# Nanite_85_SS.net
KiCad netlist of a schematic drawn in EAGLE
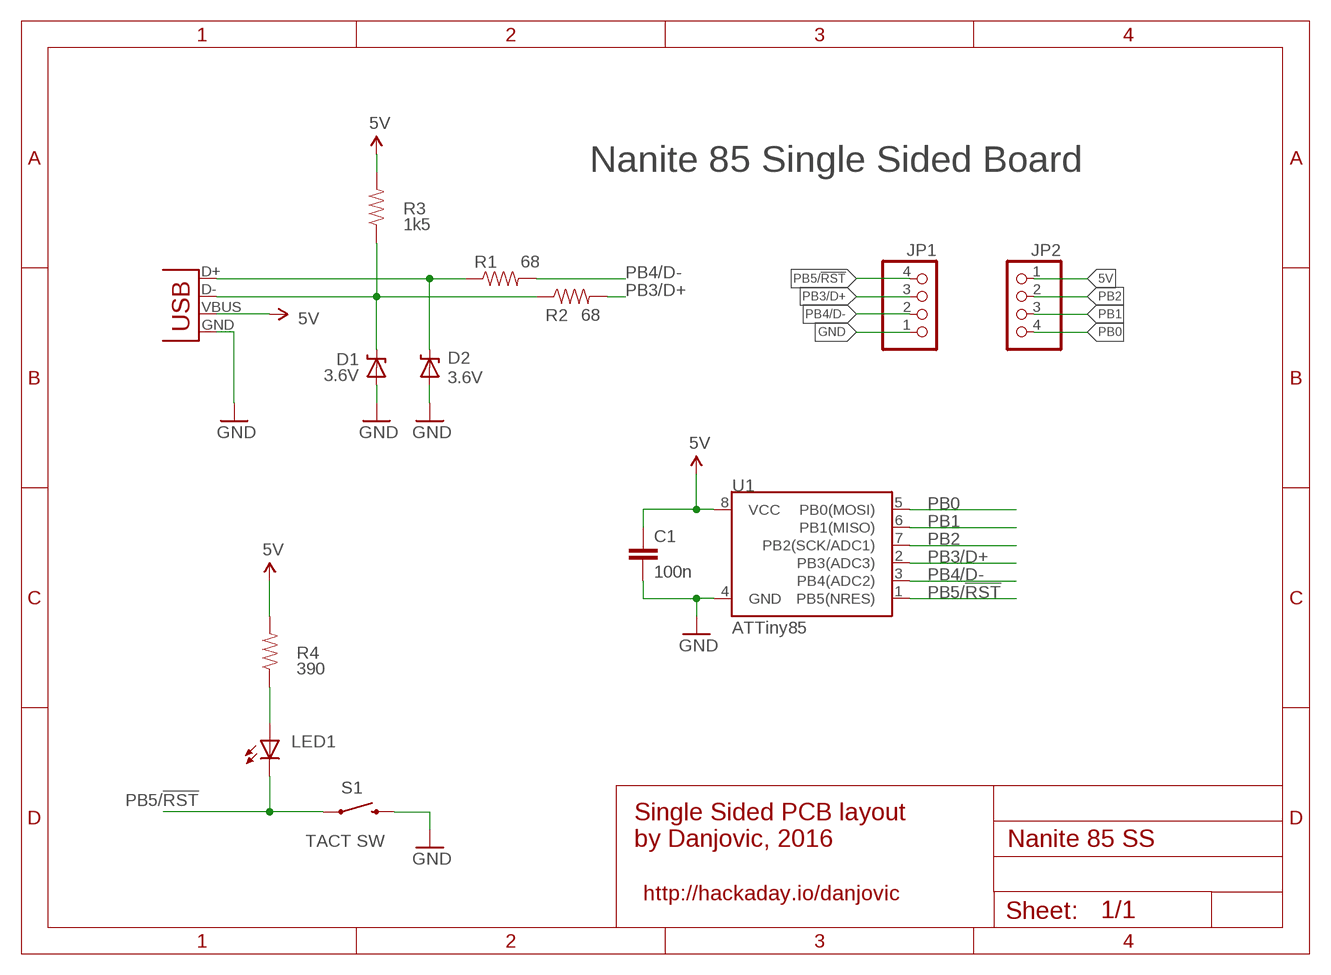
[diagram p0: schematic, sheet 1]

(export (version "E")
  (design (tool "Eeschema 10.0.6"))
  (components
    (comp (ref "C1")
      (value "100n")
      (footprint "eagle-import:CAP-PTH-SMALL-KIT")
      (libsource (lib "eagle-import") (part "CAPKIT"))
    )
    (comp (ref "D1")
      (value "3.6V")
      (footprint "eagle-import:DIODE-ZENER")
      (libsource (lib "eagle-import") (part "DIODE-ZENERPTH"))
    )
    (comp (ref "D2")
      (value "3.6V")
      (footprint "eagle-import:DIODE-ZENER")
      (libsource (lib "eagle-import") (part "DIODE-ZENERPTH"))
    )
    (comp (ref "JP1")
      (value "HEADER-1X4ROUND")
      (footprint "eagle-import:1X04_ROUND")
      (libsource (lib "eagle-import") (part "HEADER-1X4ROUND"))
    )
    (comp (ref "JP2")
      (value "HEADER-1X4ROUND")
      (footprint "eagle-import:1X04_ROUND")
      (libsource (lib "eagle-import") (part "HEADER-1X4ROUND"))
    )
    (comp (ref "JP4")
      (value "USB-B")
      (footprint "eagle-import:USB-B-PTH")
      (libsource (lib "eagle-import") (part "USBPTH"))
    )
    (comp (ref "LED1")
      (value "LED3MM")
      (footprint "eagle-import:LED3MM")
      (libsource (lib "eagle-import") (part "LED3MM"))
    )
    (comp (ref "R1")
      (value "68")
      (footprint "eagle-import:AXIAL-0.3")
      (libsource (lib "eagle-import") (part "RESISTORAXIAL-0.3"))
    )
    (comp (ref "R2")
      (value "68")
      (footprint "eagle-import:AXIAL-0.3EZ")
      (libsource (lib "eagle-import") (part "RESISTOREZ"))
    )
    (comp (ref "R3")
      (value "1k5")
      (footprint "eagle-import:AXIAL-0.3EZ")
      (libsource (lib "eagle-import") (part "RESISTOREZ"))
    )
    (comp (ref "R4")
      (value "390")
      (footprint "eagle-import:AXIAL-0.3EZ")
      (libsource (lib "eagle-import") (part "RESISTOREZ"))
    )
    (comp (ref "S1")
      (value "TACT SW")
      (footprint "eagle-import:TACTILE-PTH")
      (libsource (lib "eagle-import") (part "SWITCH-MOMENTARY-2PTH"))
    )
    (comp (ref "U1")
      (value "ATTiny85")
      (footprint "eagle-import:DIP08")
      (libsource (lib "eagle-import") (part "ATTINY45TINY45-20-DIP"))
    )
  )
  (nets
    (net (code "1") (name "/PB5{slash}~{RST}") (class "Default")
      (node (ref "JP1") (pin "4") (pinfunction "4_4") (pintype "passive"))
      (node (ref "LED1") (pin "K") (pinfunction "C_K") (pintype "passive"))
      (node (ref "S1") (pin "1") (pinfunction "1_1") (pintype "passive"))
      (node (ref "U1") (pin "1") (pinfunction "PB5(NRES)_1") (pintype "bidirectional"))
    )
    (net (code "2") (name "5V") (class "Default")
      (node (ref "C1") (pin "1") (pinfunction "1_1") (pintype "passive"))
      (node (ref "JP2") (pin "1") (pinfunction "1_1") (pintype "passive"))
      (node (ref "JP4") (pin "VBUS") (pinfunction "VBUS_VBUS") (pintype "bidirectional"))
      (node (ref "R3") (pin "P$2") (pinfunction "2_P$2") (pintype "passive"))
      (node (ref "R4") (pin "P$2") (pinfunction "2_P$2") (pintype "passive"))
      (node (ref "U1") (pin "8") (pinfunction "VCC_8") (pintype "bidirectional"))
    )
    (net (code "3") (name "GND") (class "Default")
      (node (ref "C1") (pin "2") (pinfunction "2_2") (pintype "passive"))
      (node (ref "D1") (pin "P$2") (pinfunction "A_P$2") (pintype "passive"))
      (node (ref "D2") (pin "P$2") (pinfunction "A_P$2") (pintype "passive"))
      (node (ref "JP1") (pin "1") (pinfunction "1_1") (pintype "passive"))
      (node (ref "JP4") (pin "GND") (pinfunction "GND_GND") (pintype "bidirectional"))
      (node (ref "S1") (pin "3") (pinfunction "2_3") (pintype "passive"))
      (node (ref "U1") (pin "4") (pinfunction "GND_4") (pintype "bidirectional"))
    )
    (net (code "4") (name "Net-(D1-C)") (class "Default")
      (node (ref "D1") (pin "P$1") (pinfunction "C_P$1") (pintype "passive"))
      (node (ref "JP4") (pin "D-") (pinfunction "D-_D-") (pintype "bidirectional"))
      (node (ref "R2") (pin "P$1") (pinfunction "1_P$1") (pintype "passive"))
      (node (ref "R3") (pin "P$1") (pinfunction "1_P$1") (pintype "passive"))
    )
    (net (code "5") (name "Net-(D2-C)") (class "Default")
      (node (ref "D2") (pin "P$1") (pinfunction "C_P$1") (pintype "passive"))
      (node (ref "JP4") (pin "D+") (pinfunction "D+_D+") (pintype "bidirectional"))
      (node (ref "R1") (pin "P$1") (pinfunction "1_P$1") (pintype "passive"))
    )
    (net (code "6") (name "Net-(R4-1)") (class "Default")
      (node (ref "LED1") (pin "A") (pinfunction "A_A") (pintype "passive"))
      (node (ref "R4") (pin "P$1") (pinfunction "1_P$1") (pintype "passive"))
    )
    (net (code "7") (name "PB0") (class "Default")
      (node (ref "JP2") (pin "4") (pinfunction "4_4") (pintype "passive"))
      (node (ref "U1") (pin "5") (pinfunction "PB0(MOSI)_5") (pintype "bidirectional"))
    )
    (net (code "8") (name "PB1") (class "Default")
      (node (ref "JP2") (pin "3") (pinfunction "3_3") (pintype "passive"))
      (node (ref "U1") (pin "6") (pinfunction "PB1(MISO)_6") (pintype "bidirectional"))
    )
    (net (code "9") (name "PB2") (class "Default")
      (node (ref "JP2") (pin "2") (pinfunction "2_2") (pintype "passive"))
      (node (ref "U1") (pin "7") (pinfunction "PB2(SCK/ADC1)_7") (pintype "bidirectional"))
    )
    (net (code "10") (name "PB3{slash}D+") (class "Default")
      (node (ref "JP1") (pin "3") (pinfunction "3_3") (pintype "passive"))
      (node (ref "R2") (pin "P$2") (pinfunction "2_P$2") (pintype "passive"))
      (node (ref "U1") (pin "2") (pinfunction "PB3(ADC3)_2") (pintype "bidirectional"))
    )
    (net (code "11") (name "PB4{slash}D-") (class "Default")
      (node (ref "JP1") (pin "2") (pinfunction "2_2") (pintype "passive"))
      (node (ref "R1") (pin "P$2") (pinfunction "2_P$2") (pintype "passive"))
      (node (ref "U1") (pin "3") (pinfunction "PB4(ADC2)_3") (pintype "bidirectional"))
    )
  )
)
